# Grove_-_Single_Axis_Analog_Gyro_v1_0.net
KiCad netlist of a schematic drawn in EAGLE
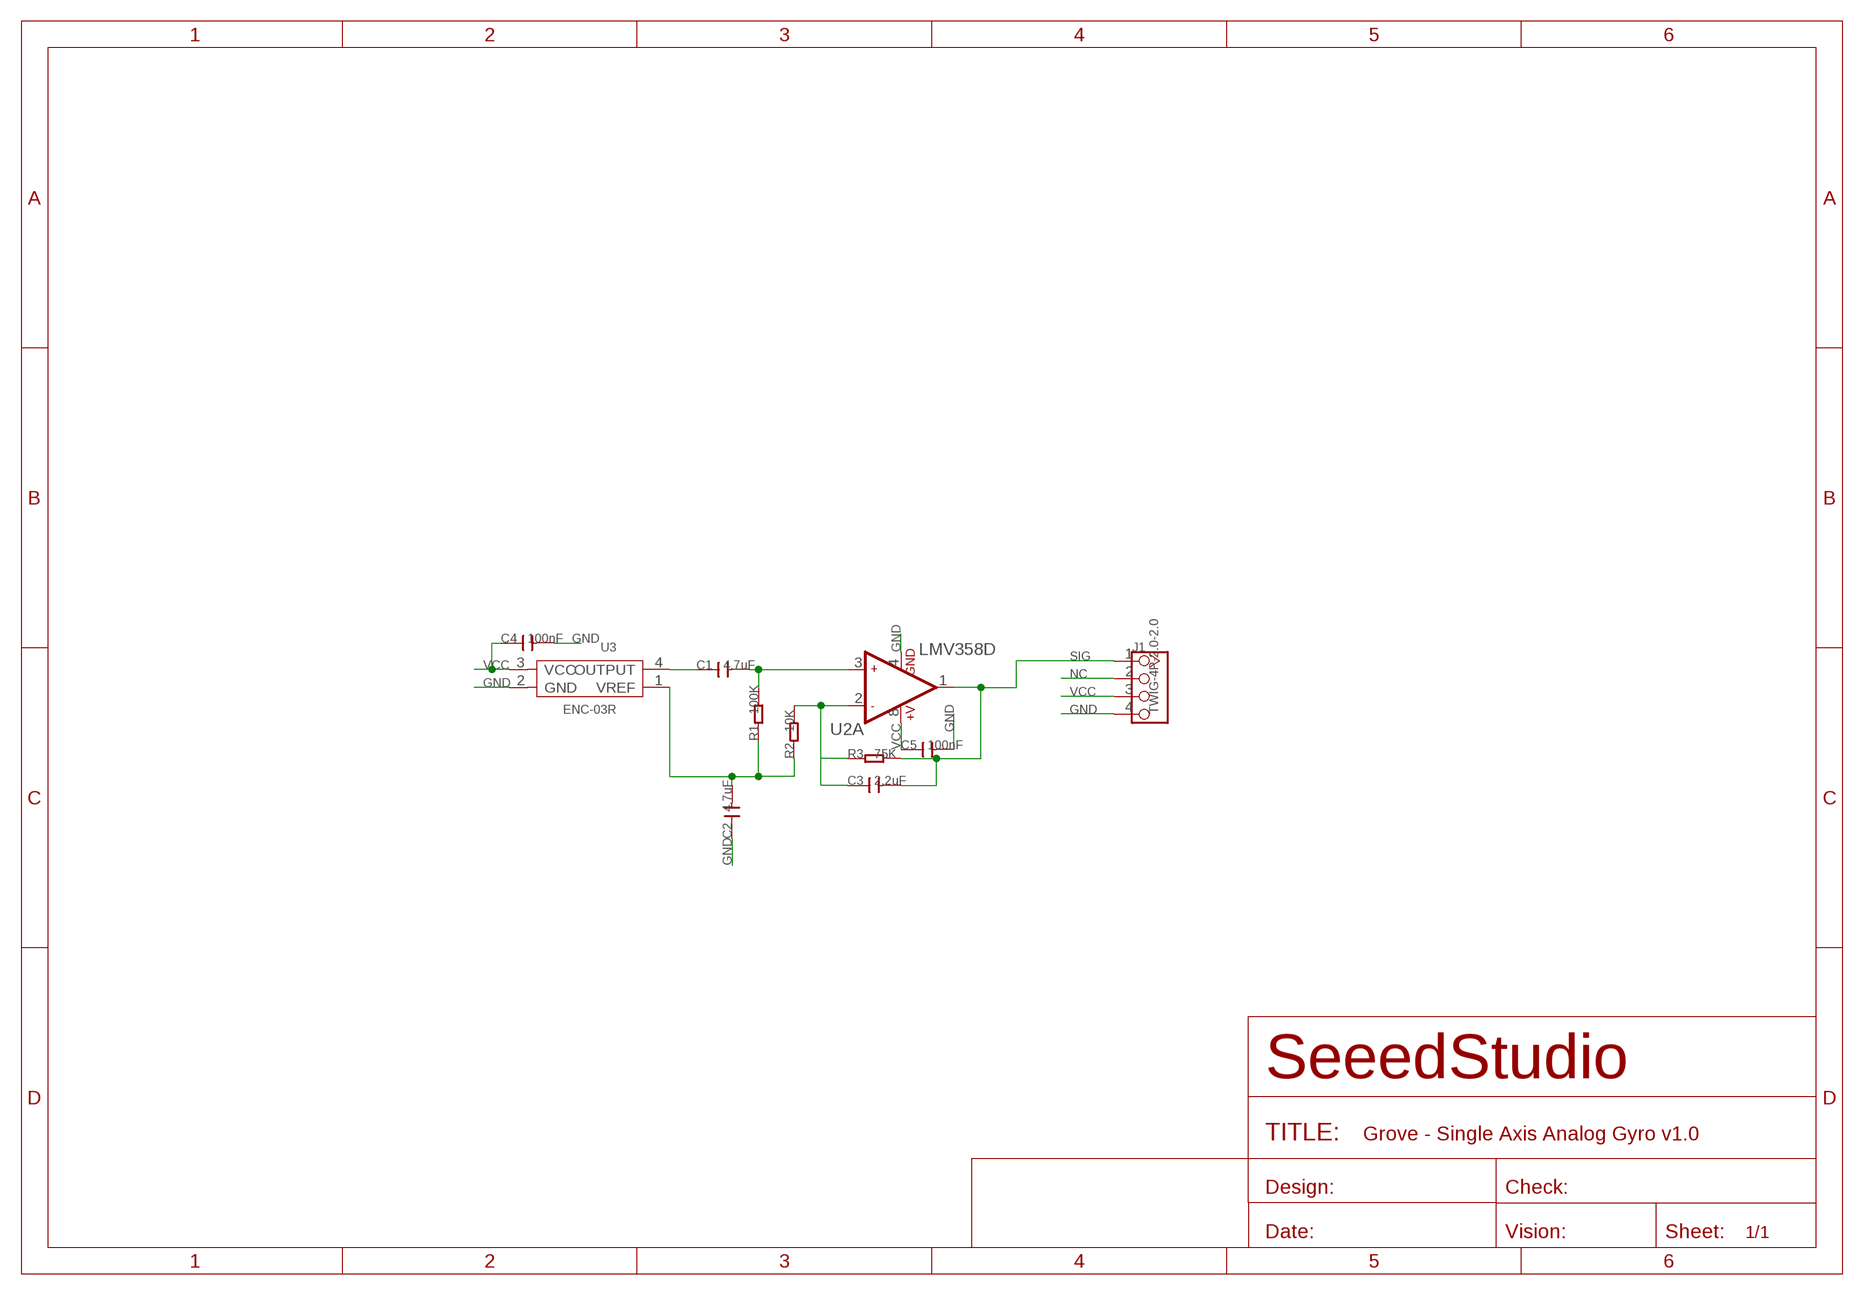
[diagram p0: schematic, sheet 1]

(export (version "E")
  (design (tool "Eeschema 10.0.6"))
  (components
    (comp (ref "C1")
      (value "4.7uF")
      (footprint "eagle-import:C0805")
      (libsource (lib "eagle-import") (part "C-0805"))
    )
    (comp (ref "C2")
      (value "4.7uF")
      (footprint "eagle-import:C0805")
      (libsource (lib "eagle-import") (part "C-0805"))
    )
    (comp (ref "C3")
      (value "2.2uF")
      (footprint "eagle-import:C0805")
      (libsource (lib "eagle-import") (part "C-0805"))
    )
    (comp (ref "C4")
      (value "100nF")
      (footprint "eagle-import:C0603")
      (libsource (lib "eagle-import") (part "C-0603"))
    )
    (comp (ref "C5")
      (value "100nF")
      (footprint "eagle-import:C0603")
      (libsource (lib "eagle-import") (part "C-0603"))
    )
    (comp (ref "J1")
      (value "TWIG-4P-2.0-2.0")
      (footprint "eagle-import:4P-2.0")
      (libsource (lib "eagle-import") (part "TWIG-4P-2.0-2.0"))
    )
    (comp (ref "R1")
      (value "100K")
      (footprint "eagle-import:R0603")
      (libsource (lib "eagle-import") (part "R-0603"))
    )
    (comp (ref "R2")
      (value "10K")
      (footprint "eagle-import:R0603")
      (libsource (lib "eagle-import") (part "R-0603"))
    )
    (comp (ref "R3")
      (value "75K")
      (footprint "eagle-import:R0603")
      (libsource (lib "eagle-import") (part "R-0603"))
    )
    (comp (ref "U2")
      (value "LMV358D")
      (footprint "eagle-import:SO08")
      (libsource (lib "eagle-import") (part "LMV358D"))
    )
    (comp (ref "U3")
      (value "ENC-03R")
      (footprint "eagle-import:4P-SMD-8X4X2H")
      (libsource (lib "eagle-import") (part "ENC-03R'ENC-03RC-R'"))
    )
  )
  (nets
    (net (code "1") (name "/GND") (class "Default")
      (node (ref "C2") (pin "1") (pinfunction "1_1") (pintype "passive"))
      (node (ref "C4") (pin "2") (pinfunction "2_2") (pintype "passive"))
      (node (ref "C5") (pin "2") (pinfunction "2_2") (pintype "passive"))
      (node (ref "J1") (pin "4") (pinfunction "4_4") (pintype "bidirectional"))
      (node (ref "U2") (pin "4") (pinfunction "GND_4") (pintype "power_in"))
      (node (ref "U3") (pin "2") (pinfunction "GND_2") (pintype "bidirectional"))
    )
    (net (code "2") (name "/NC") (class "Default")
      (node (ref "J1") (pin "2") (pinfunction "2_2") (pintype "bidirectional"))
    )
    (net (code "3") (name "/SIG") (class "Default")
      (node (ref "C3") (pin "2") (pinfunction "2_2") (pintype "passive"))
      (node (ref "J1") (pin "1") (pinfunction "1_1") (pintype "bidirectional"))
      (node (ref "R3") (pin "2") (pinfunction "2_2") (pintype "passive"))
      (node (ref "U2") (pin "1") (pinfunction "OUT1_1") (pintype "output"))
    )
    (net (code "4") (name "/VCC") (class "Default")
      (node (ref "C4") (pin "1") (pinfunction "1_1") (pintype "passive"))
      (node (ref "C5") (pin "1") (pinfunction "1_1") (pintype "passive"))
      (node (ref "J1") (pin "3") (pinfunction "3_3") (pintype "bidirectional"))
      (node (ref "U2") (pin "8") (pinfunction "+V_8") (pintype "power_in"))
      (node (ref "U3") (pin "3") (pinfunction "VCC_3") (pintype "bidirectional"))
    )
    (net (code "5") (name "Net-(U2A-+IN1)") (class "Default")
      (node (ref "C1") (pin "2") (pinfunction "2_2") (pintype "passive"))
      (node (ref "R1") (pin "2") (pinfunction "2_2") (pintype "passive"))
      (node (ref "U2") (pin "3") (pinfunction "+IN1_3") (pintype "input"))
    )
    (net (code "6") (name "Net-(U2A--IN1)") (class "Default")
      (node (ref "C3") (pin "1") (pinfunction "1_1") (pintype "passive"))
      (node (ref "R2") (pin "2") (pinfunction "2_2") (pintype "passive"))
      (node (ref "R3") (pin "1") (pinfunction "1_1") (pintype "passive"))
      (node (ref "U2") (pin "2") (pinfunction "-IN1_2") (pintype "input"))
    )
    (net (code "7") (name "Net-(U3-OUTPUT)") (class "Default")
      (node (ref "C1") (pin "1") (pinfunction "1_1") (pintype "passive"))
      (node (ref "U3") (pin "4") (pinfunction "OUTPUT_4") (pintype "bidirectional"))
    )
    (net (code "8") (name "Net-(U3-VREF)") (class "Default")
      (node (ref "C2") (pin "2") (pinfunction "2_2") (pintype "passive"))
      (node (ref "R1") (pin "1") (pinfunction "1_1") (pintype "passive"))
      (node (ref "R2") (pin "1") (pinfunction "1_1") (pintype "passive"))
      (node (ref "U3") (pin "1") (pinfunction "VREF_1") (pintype "bidirectional"))
    )
  )
)
